# MAX1493.net
KiCad netlist of a schematic drawn in EAGLE
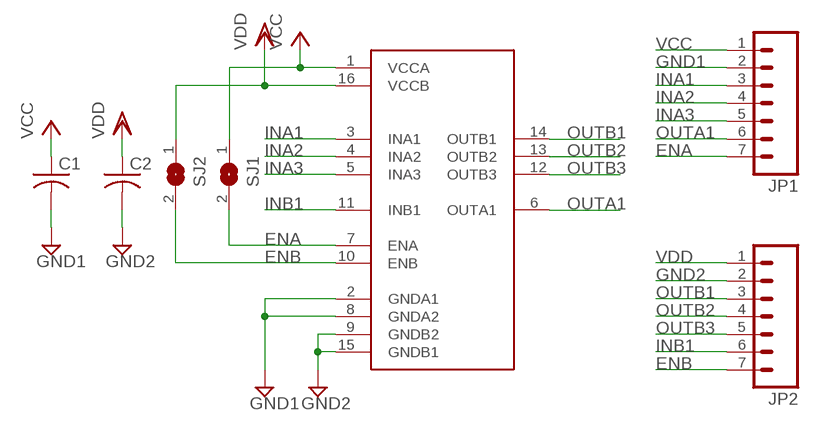
[diagram p0: schematic, sheet 2]

(export (version "E")
  (design (tool "Eeschema 10.0.6"))
  (components
    (comp (ref "C1")
      (value "C-USC0805")
      (footprint "eagle-import:C0805")
      (libsource (lib "eagle-import") (part "C-USC0805"))
    )
    (comp (ref "C2")
      (value "C-USC0805")
      (footprint "eagle-import:C0805")
      (libsource (lib "eagle-import") (part "C-USC0805"))
    )
    (comp (ref "JP1")
      (value "M07LOCK")
      (footprint "eagle-import:1X07_LOCK")
      (libsource (lib "eagle-import") (part "M07LOCK"))
    )
    (comp (ref "JP2")
      (value "M07LOCK")
      (footprint "eagle-import:1X07_LOCK")
      (libsource (lib "eagle-import") (part "M07LOCK"))
    )
    (comp (ref "SJ1") (value "SJ") (footprint "eagle-import:SJ") (libsource (lib "eagle-import") (part "SJ")))
    (comp (ref "SJ2") (value "SJ") (footprint "eagle-import:SJ") (libsource (lib "eagle-import") (part "SJ")))
    (comp (ref "U$1")
      (value "MAX14931")
      (footprint "eagle-import:SO16")
      (libsource (lib "eagle-import") (part "MAX14931"))
    )
  )
  (nets
    (net (code "1") (name "ENA") (class "Default")
      (node (ref "JP1") (pin "7") (pinfunction "7_7") (pintype "passive"))
      (node (ref "SJ1") (pin "2") (pinfunction "2_2") (pintype "passive"))
      (node (ref "U$1") (pin "7") (pinfunction "ENA_7") (pintype "input"))
    )
    (net (code "2") (name "ENB") (class "Default")
      (node (ref "JP2") (pin "7") (pinfunction "7_7") (pintype "passive"))
      (node (ref "SJ2") (pin "2") (pinfunction "2_2") (pintype "passive"))
      (node (ref "U$1") (pin "10") (pinfunction "ENB_10") (pintype "input"))
    )
    (net (code "3") (name "GND1") (class "Default")
      (node (ref "C1") (pin "2") (pinfunction "2_2") (pintype "passive"))
      (node (ref "JP1") (pin "2") (pinfunction "2_2") (pintype "passive"))
      (node (ref "U$1") (pin "2") (pinfunction "GNDA1_2") (pintype "power_in"))
      (node (ref "U$1") (pin "8") (pinfunction "GNDA2_8") (pintype "power_in"))
    )
    (net (code "4") (name "GND2") (class "Default")
      (node (ref "C2") (pin "2") (pinfunction "2_2") (pintype "passive"))
      (node (ref "JP2") (pin "2") (pinfunction "2_2") (pintype "passive"))
      (node (ref "U$1") (pin "15") (pinfunction "GNDB1_15") (pintype "power_in"))
      (node (ref "U$1") (pin "9") (pinfunction "GNDB2_9") (pintype "power_in"))
    )
    (net (code "5") (name "INA1") (class "Default")
      (node (ref "JP1") (pin "3") (pinfunction "3_3") (pintype "passive"))
      (node (ref "U$1") (pin "3") (pinfunction "INA1_3") (pintype "input"))
    )
    (net (code "6") (name "INA2") (class "Default")
      (node (ref "JP1") (pin "4") (pinfunction "4_4") (pintype "passive"))
      (node (ref "U$1") (pin "4") (pinfunction "INA2_4") (pintype "input"))
    )
    (net (code "7") (name "INA3") (class "Default")
      (node (ref "JP1") (pin "5") (pinfunction "5_5") (pintype "passive"))
      (node (ref "U$1") (pin "5") (pinfunction "INA3_5") (pintype "input"))
    )
    (net (code "8") (name "INB1") (class "Default")
      (node (ref "JP2") (pin "6") (pinfunction "6_6") (pintype "passive"))
      (node (ref "U$1") (pin "11") (pinfunction "INB1_11") (pintype "input"))
    )
    (net (code "9") (name "OUTA1") (class "Default")
      (node (ref "JP1") (pin "6") (pinfunction "6_6") (pintype "passive"))
      (node (ref "U$1") (pin "6") (pinfunction "OUTA1_6") (pintype "output"))
    )
    (net (code "10") (name "OUTB1") (class "Default")
      (node (ref "JP2") (pin "3") (pinfunction "3_3") (pintype "passive"))
      (node (ref "U$1") (pin "14") (pinfunction "OUTB1_14") (pintype "output"))
    )
    (net (code "11") (name "OUTB2") (class "Default")
      (node (ref "JP2") (pin "4") (pinfunction "4_4") (pintype "passive"))
      (node (ref "U$1") (pin "13") (pinfunction "OUTB2_13") (pintype "output"))
    )
    (net (code "12") (name "OUTB3") (class "Default")
      (node (ref "JP2") (pin "5") (pinfunction "5_5") (pintype "passive"))
      (node (ref "U$1") (pin "12") (pinfunction "OUTB3_12") (pintype "output"))
    )
    (net (code "13") (name "VCC") (class "Default")
      (node (ref "C1") (pin "1") (pinfunction "1_1") (pintype "passive"))
      (node (ref "JP1") (pin "1") (pinfunction "1_1") (pintype "passive"))
      (node (ref "SJ1") (pin "1") (pinfunction "1_1") (pintype "passive"))
      (node (ref "U$1") (pin "1") (pinfunction "VCCA_1") (pintype "power_in"))
    )
    (net (code "14") (name "VDD") (class "Default")
      (node (ref "C2") (pin "1") (pinfunction "1_1") (pintype "passive"))
      (node (ref "JP2") (pin "1") (pinfunction "1_1") (pintype "passive"))
      (node (ref "SJ2") (pin "1") (pinfunction "1_1") (pintype "passive"))
      (node (ref "U$1") (pin "16") (pinfunction "VCCB_16") (pintype "power_in"))
    )
  )
)
